# USB-Hub.net
KiCad netlist of a schematic drawn in EasyEDA
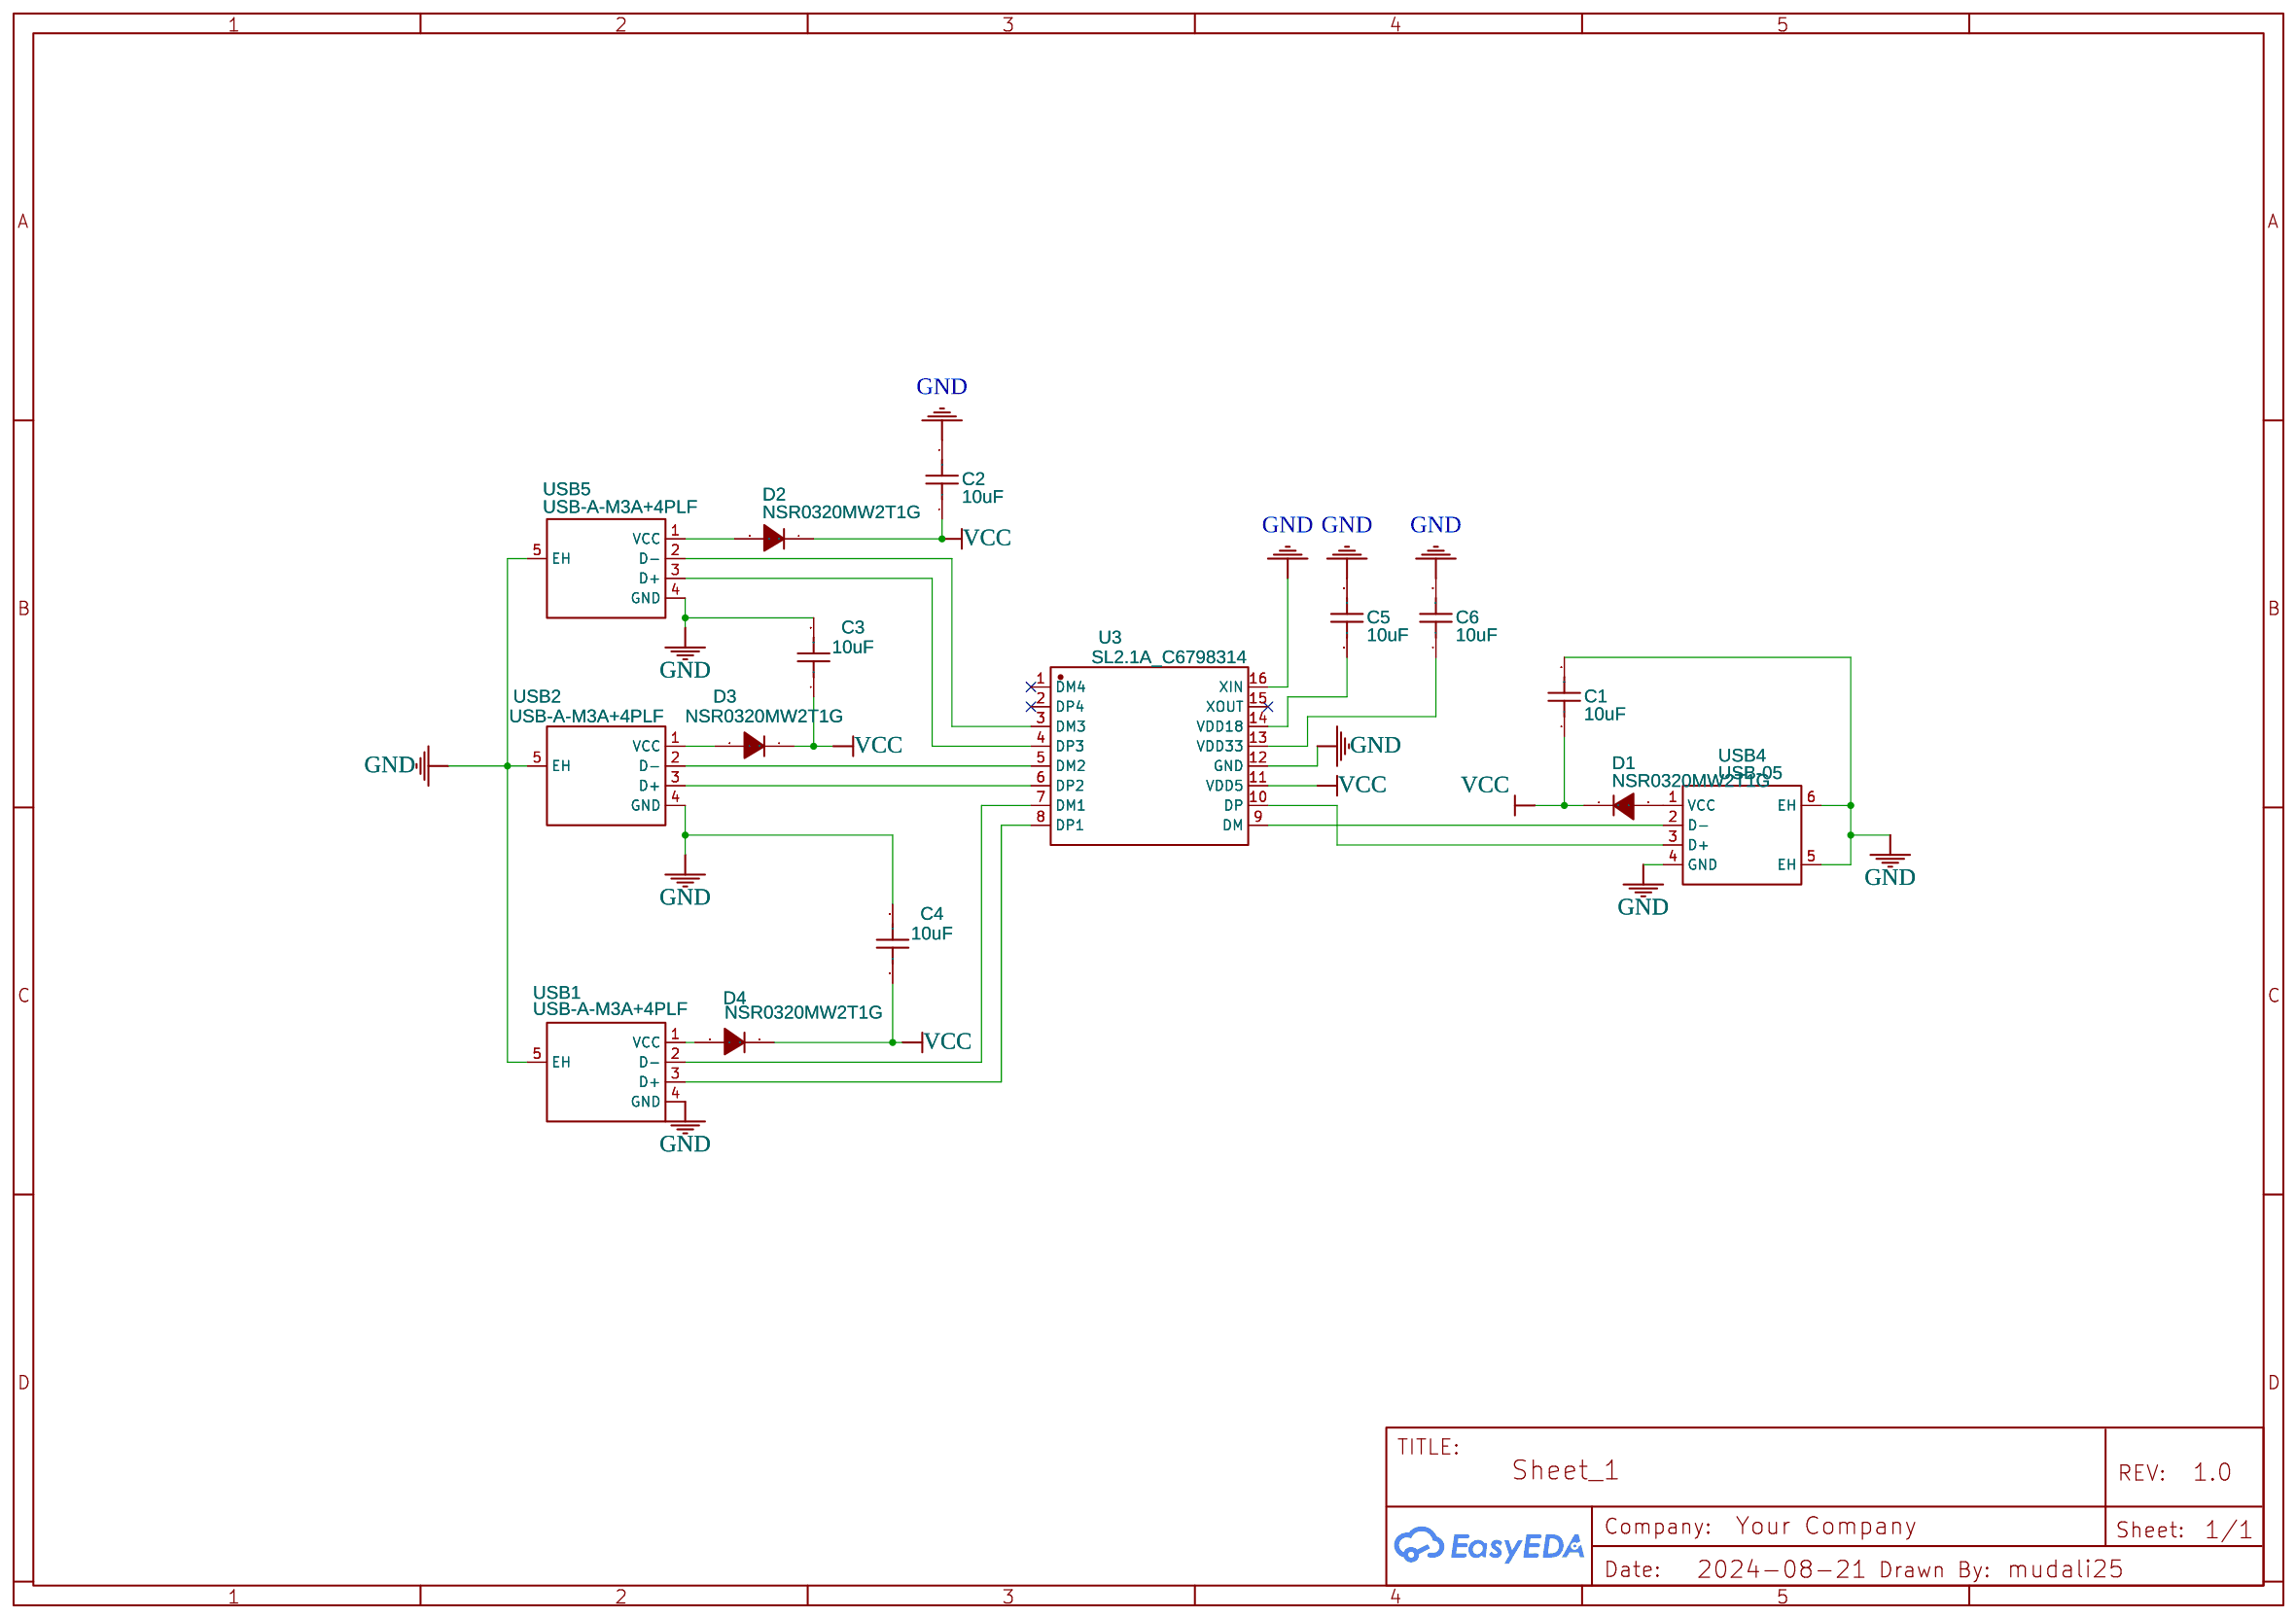
[diagram p0: schematic sheet]

(export (version "E")
  (design (tool "Eeschema 10.0.6"))
  (components
    (comp (ref "C1")
      (value "10uF")
      (fields
        (field (name "Manufacturer Part") "CL10A106KP8NNNC")
        (field (name "Manufacturer") "SAMSUNG(三星)")
      )
      (libsource (lib "") (part "CL10A106KP8NNNC"))
    )
    (comp (ref "C2")
      (value "10uF")
      (fields
        (field (name "Manufacturer Part") "CL10A106KP8NNNC")
        (field (name "Manufacturer") "SAMSUNG(三星)")
      )
      (libsource (lib "") (part "CL10A106KP8NNNC"))
    )
    (comp (ref "C3")
      (value "10uF")
      (fields
        (field (name "Manufacturer Part") "CL10A106KP8NNNC")
        (field (name "Manufacturer") "SAMSUNG(三星)")
      )
      (libsource (lib "") (part "CL10A106KP8NNNC"))
    )
    (comp (ref "C4")
      (value "10uF")
      (fields
        (field (name "Manufacturer Part") "CL10A106KP8NNNC")
        (field (name "Manufacturer") "SAMSUNG(三星)")
      )
      (libsource (lib "") (part "CL10A106KP8NNNC"))
    )
    (comp (ref "C5")
      (value "10uF")
      (fields
        (field (name "Manufacturer Part") "CL10A106KP8NNNC")
        (field (name "Manufacturer") "SAMSUNG(三星)")
      )
      (libsource (lib "") (part "CL10A106KP8NNNC"))
    )
    (comp (ref "C6")
      (value "10uF")
      (fields
        (field (name "Manufacturer Part") "CL10A106KP8NNNC")
        (field (name "Manufacturer") "SAMSUNG(三星)")
      )
      (libsource (lib "") (part "CL10A106KP8NNNC"))
    )
    (comp (ref "D1")
      (value "NSR0320MW2T1G")
      (fields (field (name "Manufacturer") "onsemi(安森美)"))
      (libsource (lib "") (part "NSR0320MW2T1G"))
    )
    (comp (ref "D2")
      (value "NSR0320MW2T1G")
      (fields (field (name "Manufacturer") "onsemi(安森美)"))
      (libsource (lib "") (part "NSR0320MW2T1G_1"))
    )
    (comp (ref "D3")
      (value "NSR0320MW2T1G")
      (fields (field (name "Manufacturer") "onsemi(安森美)"))
      (libsource (lib "") (part "NSR0320MW2T1G_1"))
    )
    (comp (ref "D4")
      (value "NSR0320MW2T1G")
      (fields (field (name "Manufacturer") "onsemi(安森美)"))
      (libsource (lib "") (part "NSR0320MW2T1G_1"))
    )
    (comp (ref "U3")
      (value "SL2.1A_C6798314")
      (fields (field (name "Manufacturer Part") "SL2.1A") (field (name "Manufacturer") "CoreChips(和芯润德)"))
      (libsource (lib "") (part "SL2.1A_C6798314"))
    )
    (comp (ref "USB1")
      (value "USB-A-M3A+4PLF")
      (fields (field (name "Manufacturer") "JINJIA(金佳)"))
      (libsource (lib "") (part "USB-A-M3A+4PLF"))
    )
    (comp (ref "USB2")
      (value "USB-A-M3A+4PLF")
      (fields (field (name "Manufacturer") "JINJIA(金佳)"))
      (libsource (lib "") (part "USB-A-M3A+4PLF"))
    )
    (comp (ref "USB4")
      (value "USB-05")
      (fields (field (name "Manufacturer") "SOFNG(硕方)"))
      (libsource (lib "") (part "USB-05"))
    )
    (comp (ref "USB5")
      (value "USB-A-M3A+4PLF")
      (fields (field (name "Manufacturer") "JINJIA(金佳)"))
      (libsource (lib "") (part "USB-A-M3A+4PLF"))
    )
  )
  (nets
    (net (code "1") (name "GND") (class "Default")
      (node (ref "C1") (pin "2") (pinfunction "2_2") (pintype "unspecified"))
      (node (ref "C2") (pin "2") (pinfunction "2_2") (pintype "unspecified"))
      (node (ref "C3") (pin "2") (pinfunction "2_2") (pintype "unspecified"))
      (node (ref "C4") (pin "2") (pinfunction "2_2") (pintype "unspecified"))
      (node (ref "C5") (pin "2") (pinfunction "2_2") (pintype "unspecified"))
      (node (ref "C6") (pin "2") (pinfunction "2_2") (pintype "unspecified"))
      (node (ref "U3") (pin "12") (pinfunction "GND_12") (pintype "unspecified"))
      (node (ref "U3") (pin "16") (pinfunction "XIN_16") (pintype "unspecified"))
      (node (ref "USB1") (pin "4") (pinfunction "GND_4") (pintype "input"))
      (node (ref "USB1") (pin "5") (pinfunction "EH_5") (pintype "unspecified"))
      (node (ref "USB2") (pin "4") (pinfunction "GND_4") (pintype "input"))
      (node (ref "USB2") (pin "5") (pinfunction "EH_5") (pintype "unspecified"))
      (node (ref "USB4") (pin "4") (pinfunction "GND_4") (pintype "input"))
      (node (ref "USB4") (pin "5") (pinfunction "EH_5") (pintype "unspecified"))
      (node (ref "USB4") (pin "6") (pinfunction "EH_6") (pintype "unspecified"))
      (node (ref "USB5") (pin "4") (pinfunction "GND_4") (pintype "input"))
      (node (ref "USB5") (pin "5") (pinfunction "EH_5") (pintype "unspecified"))
    )
    (net (code "2") (name "Net-(D1-A)") (class "Default")
      (node (ref "D1") (pin "2") (pinfunction "A_2") (pintype "unspecified"))
      (node (ref "USB4") (pin "1") (pinfunction "VCC_1") (pintype "input"))
    )
    (net (code "3") (name "Net-(D2-A)") (class "Default")
      (node (ref "D2") (pin "2") (pinfunction "A_2") (pintype "unspecified"))
      (node (ref "USB5") (pin "1") (pinfunction "VCC_1") (pintype "input"))
    )
    (net (code "4") (name "Net-(D3-A)") (class "Default")
      (node (ref "D3") (pin "2") (pinfunction "A_2") (pintype "unspecified"))
      (node (ref "USB2") (pin "1") (pinfunction "VCC_1") (pintype "input"))
    )
    (net (code "5") (name "Net-(D4-A)") (class "Default")
      (node (ref "D4") (pin "2") (pinfunction "A_2") (pintype "unspecified"))
      (node (ref "USB1") (pin "1") (pinfunction "VCC_1") (pintype "input"))
    )
    (net (code "6") (name "Net-(U3-DM)") (class "Default")
      (node (ref "U3") (pin "9") (pinfunction "DM_9") (pintype "unspecified"))
      (node (ref "USB4") (pin "2") (pinfunction "D-_2") (pintype "input"))
    )
    (net (code "7") (name "Net-(U3-DM1)") (class "Default")
      (node (ref "U3") (pin "7") (pinfunction "DM1_7") (pintype "unspecified"))
      (node (ref "USB1") (pin "2") (pinfunction "D-_2") (pintype "input"))
    )
    (net (code "8") (name "Net-(U3-DM2)") (class "Default")
      (node (ref "U3") (pin "5") (pinfunction "DM2_5") (pintype "unspecified"))
      (node (ref "USB2") (pin "2") (pinfunction "D-_2") (pintype "input"))
    )
    (net (code "9") (name "Net-(U3-DM3)") (class "Default")
      (node (ref "U3") (pin "3") (pinfunction "DM3_3") (pintype "unspecified"))
      (node (ref "USB5") (pin "2") (pinfunction "D-_2") (pintype "input"))
    )
    (net (code "10") (name "Net-(U3-DP)") (class "Default")
      (node (ref "U3") (pin "10") (pinfunction "DP_10") (pintype "unspecified"))
      (node (ref "USB4") (pin "3") (pinfunction "D+_3") (pintype "input"))
    )
    (net (code "11") (name "Net-(U3-DP1)") (class "Default")
      (node (ref "U3") (pin "8") (pinfunction "DP1_8") (pintype "unspecified"))
      (node (ref "USB1") (pin "3") (pinfunction "D+_3") (pintype "input"))
    )
    (net (code "12") (name "Net-(U3-DP2)") (class "Default")
      (node (ref "U3") (pin "6") (pinfunction "DP2_6") (pintype "unspecified"))
      (node (ref "USB2") (pin "3") (pinfunction "D+_3") (pintype "input"))
    )
    (net (code "13") (name "Net-(U3-DP3)") (class "Default")
      (node (ref "U3") (pin "4") (pinfunction "DP3_4") (pintype "unspecified"))
      (node (ref "USB5") (pin "3") (pinfunction "D+_3") (pintype "input"))
    )
    (net (code "14") (name "Net-(U3-VDD18)") (class "Default")
      (node (ref "C5") (pin "1") (pinfunction "1_1") (pintype "unspecified"))
      (node (ref "U3") (pin "14") (pinfunction "VDD18_14") (pintype "unspecified"))
    )
    (net (code "15") (name "Net-(U3-VDD33)") (class "Default")
      (node (ref "C6") (pin "1") (pinfunction "1_1") (pintype "unspecified"))
      (node (ref "U3") (pin "13") (pinfunction "VDD33_13") (pintype "unspecified"))
    )
    (net (code "16") (name "VCC") (class "Default")
      (node (ref "C1") (pin "1") (pinfunction "1_1") (pintype "unspecified"))
      (node (ref "C2") (pin "1") (pinfunction "1_1") (pintype "unspecified"))
      (node (ref "C3") (pin "1") (pinfunction "1_1") (pintype "unspecified"))
      (node (ref "C4") (pin "1") (pinfunction "1_1") (pintype "unspecified"))
      (node (ref "D1") (pin "1") (pinfunction "C_1") (pintype "unspecified"))
      (node (ref "D2") (pin "1") (pinfunction "C_1") (pintype "unspecified"))
      (node (ref "D3") (pin "1") (pinfunction "C_1") (pintype "unspecified"))
      (node (ref "D4") (pin "1") (pinfunction "C_1") (pintype "unspecified"))
      (node (ref "U3") (pin "11") (pinfunction "VDD5_11") (pintype "unspecified"))
    )
    (net (code "17") (name "unconnected-(U3-DM4-Pad1)") (class "Default")
      (node (ref "U3") (pin "1") (pinfunction "DM4_1") (pintype "unspecified+no_connect"))
    )
    (net (code "18") (name "unconnected-(U3-DP4-Pad2)") (class "Default")
      (node (ref "U3") (pin "2") (pinfunction "DP4_2") (pintype "unspecified+no_connect"))
    )
    (net (code "19") (name "unconnected-(U3-XOUT-Pad15)") (class "Default")
      (node (ref "U3") (pin "15") (pinfunction "XOUT_15") (pintype "unspecified+no_connect"))
    )
  )
)
